# IMU.net
KiCad netlist of a schematic drawn in Altium Designer
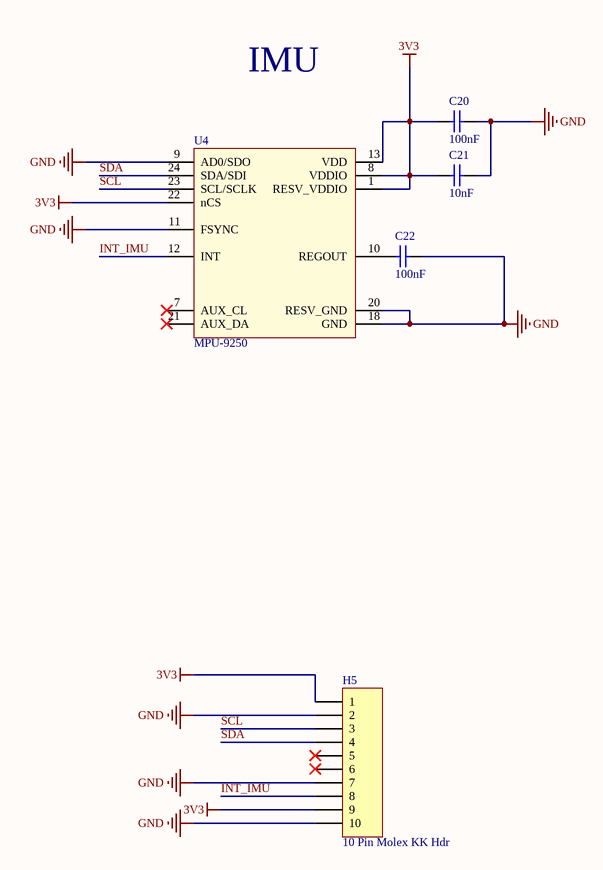
[diagram p0: IMU.SchDoc]

(export (version "E")
  (design (tool "Eeschema 10.0.6"))
  (components
    (comp (ref "C20")
      (value "100nF")
      (footprint "CAPC1608L")
      (description "CAP CER 100nF X7R +-10% 50V 0603")
      (libsource (lib "ECE AD19Components_19V1") (part "CC_100nF_0603"))
    )
    (comp (ref "C21")
      (value "10nF")
      (footprint "CAPC1608L")
      (description "CAP CER 10nF X7R +-10% 50V 0603")
      (libsource (lib "ECE AD19Components_19V1") (part "CC_10nF_0603"))
    )
    (comp (ref "C22")
      (value "100nF")
      (footprint "CAPC1608L")
      (description "CAP CER 100nF X7R +-10% 50V 0603")
      (libsource (lib "ECE AD19Components_19V1") (part "CC_100nF_0603"))
    )
    (comp (ref "H5")
      (value "10 Pin Molex KK Hdr")
      (footprint "MOLEX_KK_10_HDR")
      (description "CONN HEADER 10POS 2.54mm VERT_ Thru Hole")
      (libsource (lib "ECE AD19Components_19V1") (part "JA_MOLEX_KK_10POS"))
    )
    (comp (ref "U4")
      (value "MPU-9250")
      (footprint "Quad24")
      (description "9 axis IMU")
      (libsource (lib "ENCE461AD19_19V2") (part "MPU-9250"))
    )
  )
  (nets
    (net (code "2") (name "/INT_IMU") (class "Default")
      (node (ref "H5") (pin "8") (pinfunction "8_8") (pintype "passive"))
      (node (ref "U4") (pin "12") (pinfunction "INT_12") (pintype "passive"))
    )
    (net (code "3") (name "/SCL") (class "Default")
      (node (ref "H5") (pin "3") (pinfunction "3_3") (pintype "passive"))
      (node (ref "U4") (pin "23") (pinfunction "SCL/SCLK_23") (pintype "passive"))
    )
    (net (code "4") (name "/SDA") (class "Default")
      (node (ref "H5") (pin "4") (pinfunction "4_4") (pintype "passive"))
      (node (ref "U4") (pin "24") (pinfunction "SDA/SDI_24") (pintype "passive"))
    )
    (net (code "5") (name "3V3") (class "Default")
      (node (ref "C20") (pin "1") (pinfunction "1_1") (pintype "passive"))
      (node (ref "C21") (pin "1") (pinfunction "1_1") (pintype "passive"))
      (node (ref "H5") (pin "1") (pinfunction "1_1") (pintype "passive"))
      (node (ref "H5") (pin "9") (pinfunction "9_9") (pintype "passive"))
      (node (ref "U4") (pin "1") (pinfunction "RESV_VDDIO_1") (pintype "passive"))
      (node (ref "U4") (pin "13") (pinfunction "VDD_13") (pintype "passive"))
      (node (ref "U4") (pin "22") (pinfunction "nCS_22") (pintype "passive"))
      (node (ref "U4") (pin "8") (pinfunction "VDDIO_8") (pintype "passive"))
    )
    (net (code "6") (name "GND") (class "Default")
      (node (ref "C20") (pin "2") (pinfunction "2_2") (pintype "passive"))
      (node (ref "C21") (pin "2") (pinfunction "2_2") (pintype "passive"))
      (node (ref "C22") (pin "2") (pinfunction "2_2") (pintype "passive"))
      (node (ref "H5") (pin "10") (pinfunction "10_10") (pintype "passive"))
      (node (ref "H5") (pin "2") (pinfunction "2_2") (pintype "passive"))
      (node (ref "H5") (pin "7") (pinfunction "7_7") (pintype "passive"))
      (node (ref "U4") (pin "11") (pinfunction "FSYNC_11") (pintype "passive"))
      (node (ref "U4") (pin "18") (pinfunction "GND_18") (pintype "passive"))
      (node (ref "U4") (pin "20") (pinfunction "RESV_GND_20") (pintype "passive"))
      (node (ref "U4") (pin "9") (pinfunction "AD0/SDO_9") (pintype "passive"))
    )
    (net (code "7") (name "Net-(U4-REGOUT)") (class "Default")
      (node (ref "C22") (pin "1") (pinfunction "1_1") (pintype "passive"))
      (node (ref "U4") (pin "10") (pinfunction "REGOUT_10") (pintype "passive"))
    )
    (net (code "8") (name "unconnected-(H5-Pad5)") (class "Default")
      (node (ref "H5") (pin "5") (pinfunction "5_5") (pintype "passive+no_connect"))
    )
    (net (code "9") (name "unconnected-(H5-Pad6)") (class "Default")
      (node (ref "H5") (pin "6") (pinfunction "6_6") (pintype "passive+no_connect"))
    )
    (net (code "10") (name "unconnected-(U4-AUX_CL-Pad7)") (class "Default")
      (node (ref "U4") (pin "7") (pinfunction "AUX_CL_7") (pintype "passive+no_connect"))
    )
    (net (code "11") (name "unconnected-(U4-AUX_DA-Pad21)") (class "Default")
      (node (ref "U4") (pin "21") (pinfunction "AUX_DA_21") (pintype "passive+no_connect"))
    )
  )
)
